# RJ45_4ch_Output.net
KiCad netlist of a schematic drawn in EAGLE
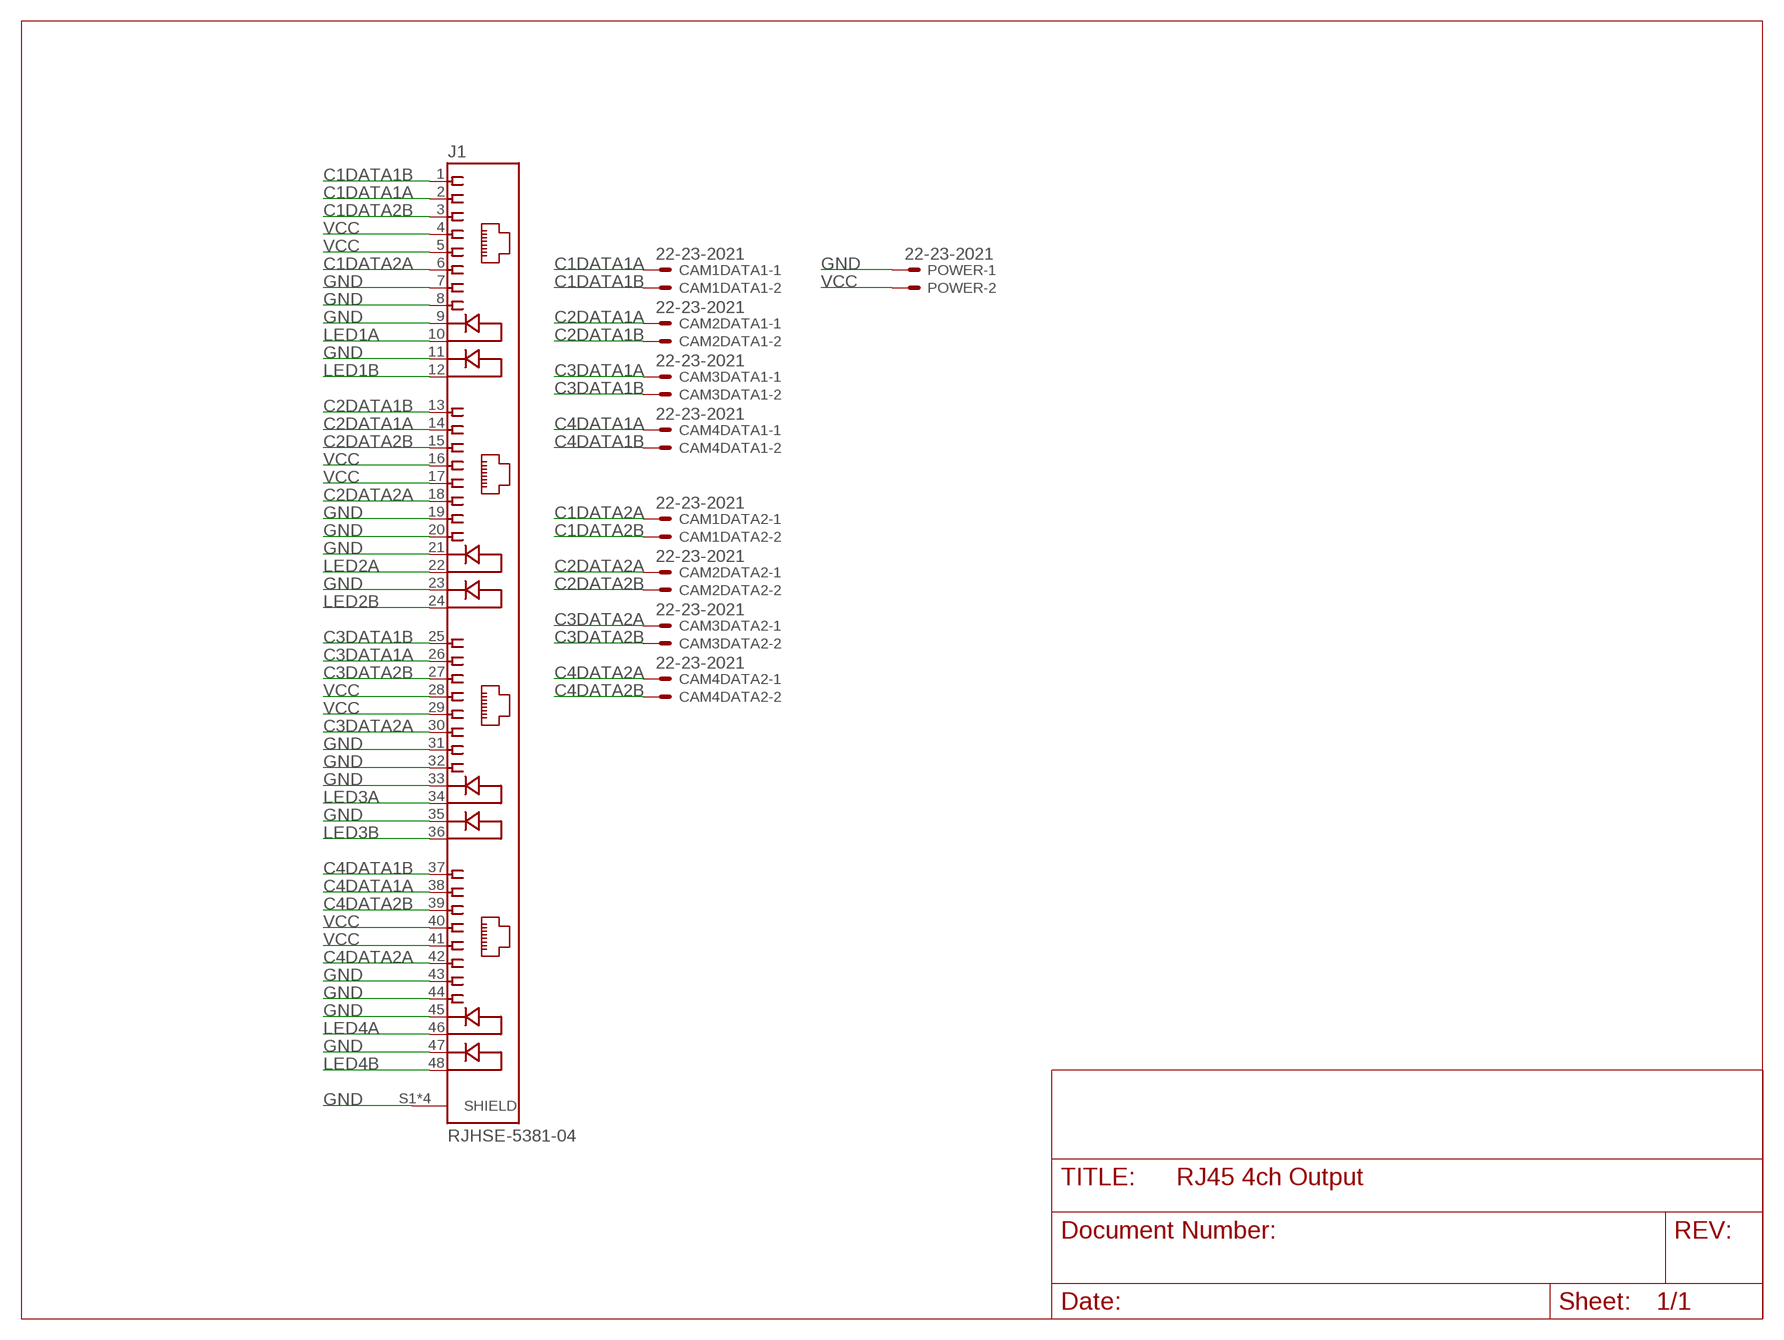
[diagram p0: schematic, sheet 1]

(export (version "E")
  (design (tool "Eeschema 10.0.6"))
  (components
    (comp (ref "CAM1DATA1")
      (value "22-23-2021")
      (footprint "eagle-import:22-23-2021")
      (fields (field (name "MF") "MOLEX"))
      (libsource (lib "eagle-import") (part "22-23-2021"))
    )
    (comp (ref "CAM1DATA2")
      (value "22-23-2021")
      (footprint "eagle-import:22-23-2021")
      (fields (field (name "MF") "MOLEX"))
      (libsource (lib "eagle-import") (part "22-23-2021"))
    )
    (comp (ref "CAM2DATA1")
      (value "22-23-2021")
      (footprint "eagle-import:22-23-2021")
      (fields (field (name "MF") "MOLEX"))
      (libsource (lib "eagle-import") (part "22-23-2021"))
    )
    (comp (ref "CAM2DATA2")
      (value "22-23-2021")
      (footprint "eagle-import:22-23-2021")
      (fields (field (name "MF") "MOLEX"))
      (libsource (lib "eagle-import") (part "22-23-2021"))
    )
    (comp (ref "CAM3DATA1")
      (value "22-23-2021")
      (footprint "eagle-import:22-23-2021")
      (fields (field (name "MF") "MOLEX"))
      (libsource (lib "eagle-import") (part "22-23-2021"))
    )
    (comp (ref "CAM3DATA2")
      (value "22-23-2021")
      (footprint "eagle-import:22-23-2021")
      (fields (field (name "MF") "MOLEX"))
      (libsource (lib "eagle-import") (part "22-23-2021"))
    )
    (comp (ref "CAM4DATA1")
      (value "22-23-2021")
      (footprint "eagle-import:22-23-2021")
      (fields (field (name "MF") "MOLEX"))
      (libsource (lib "eagle-import") (part "22-23-2021"))
    )
    (comp (ref "CAM4DATA2")
      (value "22-23-2021")
      (footprint "eagle-import:22-23-2021")
      (fields (field (name "MF") "MOLEX"))
      (libsource (lib "eagle-import") (part "22-23-2021"))
    )
    (comp (ref "J1")
      (value "RJHSE-5381-04")
      (footprint "eagle-import:AMPHENOL_RJHSE-5381-04")
      (fields (field (name "MF") "Amphenol ICC"))
      (libsource (lib "eagle-import") (part "RJHSE-5381-04"))
    )
    (comp (ref "POWER")
      (value "22-23-2021")
      (footprint "eagle-import:22-23-2021")
      (fields (field (name "MF") "MOLEX"))
      (libsource (lib "eagle-import") (part "22-23-2021"))
    )
  )
  (nets
    (net (code "1") (name "/C1DATA1A") (class "Default")
      (node (ref "CAM1DATA1") (pin "1") (pinfunction "S_1") (pintype "passive"))
      (node (ref "J1") (pin "2") (pinfunction "2_2") (pintype "passive"))
    )
    (net (code "2") (name "/C1DATA1B") (class "Default")
      (node (ref "CAM1DATA1") (pin "2") (pinfunction "S_2") (pintype "passive"))
      (node (ref "J1") (pin "1") (pinfunction "1_1") (pintype "passive"))
    )
    (net (code "3") (name "/C1DATA2A") (class "Default")
      (node (ref "CAM1DATA2") (pin "1") (pinfunction "S_1") (pintype "passive"))
      (node (ref "J1") (pin "6") (pinfunction "6_6") (pintype "passive"))
    )
    (net (code "4") (name "/C1DATA2B") (class "Default")
      (node (ref "CAM1DATA2") (pin "2") (pinfunction "S_2") (pintype "passive"))
      (node (ref "J1") (pin "3") (pinfunction "3_3") (pintype "passive"))
    )
    (net (code "5") (name "/C2DATA1A") (class "Default")
      (node (ref "CAM2DATA1") (pin "1") (pinfunction "S_1") (pintype "passive"))
      (node (ref "J1") (pin "14") (pinfunction "14_14") (pintype "passive"))
    )
    (net (code "6") (name "/C2DATA1B") (class "Default")
      (node (ref "CAM2DATA1") (pin "2") (pinfunction "S_2") (pintype "passive"))
      (node (ref "J1") (pin "13") (pinfunction "13_13") (pintype "passive"))
    )
    (net (code "7") (name "/C2DATA2A") (class "Default")
      (node (ref "CAM2DATA2") (pin "1") (pinfunction "S_1") (pintype "passive"))
      (node (ref "J1") (pin "18") (pinfunction "18_18") (pintype "passive"))
    )
    (net (code "8") (name "/C2DATA2B") (class "Default")
      (node (ref "CAM2DATA2") (pin "2") (pinfunction "S_2") (pintype "passive"))
      (node (ref "J1") (pin "15") (pinfunction "15_15") (pintype "passive"))
    )
    (net (code "9") (name "/C3DATA1A") (class "Default")
      (node (ref "CAM3DATA1") (pin "1") (pinfunction "S_1") (pintype "passive"))
      (node (ref "J1") (pin "26") (pinfunction "26_26") (pintype "passive"))
    )
    (net (code "10") (name "/C3DATA1B") (class "Default")
      (node (ref "CAM3DATA1") (pin "2") (pinfunction "S_2") (pintype "passive"))
      (node (ref "J1") (pin "25") (pinfunction "25_25") (pintype "passive"))
    )
    (net (code "11") (name "/C3DATA2A") (class "Default")
      (node (ref "CAM3DATA2") (pin "1") (pinfunction "S_1") (pintype "passive"))
      (node (ref "J1") (pin "30") (pinfunction "30_30") (pintype "passive"))
    )
    (net (code "12") (name "/C3DATA2B") (class "Default")
      (node (ref "CAM3DATA2") (pin "2") (pinfunction "S_2") (pintype "passive"))
      (node (ref "J1") (pin "27") (pinfunction "27_27") (pintype "passive"))
    )
    (net (code "13") (name "/C4DATA1A") (class "Default")
      (node (ref "CAM4DATA1") (pin "1") (pinfunction "S_1") (pintype "passive"))
      (node (ref "J1") (pin "38") (pinfunction "38_38") (pintype "passive"))
    )
    (net (code "14") (name "/C4DATA1B") (class "Default")
      (node (ref "CAM4DATA1") (pin "2") (pinfunction "S_2") (pintype "passive"))
      (node (ref "J1") (pin "37") (pinfunction "37_37") (pintype "passive"))
    )
    (net (code "15") (name "/C4DATA2A") (class "Default")
      (node (ref "CAM4DATA2") (pin "1") (pinfunction "S_1") (pintype "passive"))
      (node (ref "J1") (pin "42") (pinfunction "42_42") (pintype "passive"))
    )
    (net (code "16") (name "/C4DATA2B") (class "Default")
      (node (ref "CAM4DATA2") (pin "2") (pinfunction "S_2") (pintype "passive"))
      (node (ref "J1") (pin "39") (pinfunction "39_39") (pintype "passive"))
    )
    (net (code "17") (name "/GND") (class "Default")
      (node (ref "J1") (pin "11") (pinfunction "11_11") (pintype "passive"))
      (node (ref "J1") (pin "19") (pinfunction "19_19") (pintype "passive"))
      (node (ref "J1") (pin "20") (pinfunction "20_20") (pintype "passive"))
      (node (ref "J1") (pin "21") (pinfunction "21_21") (pintype "passive"))
      (node (ref "J1") (pin "23") (pinfunction "23_23") (pintype "passive"))
      (node (ref "J1") (pin "31") (pinfunction "31_31") (pintype "passive"))
      (node (ref "J1") (pin "32") (pinfunction "32_32") (pintype "passive"))
      (node (ref "J1") (pin "33") (pinfunction "33_33") (pintype "passive"))
      (node (ref "J1") (pin "35") (pinfunction "35_35") (pintype "passive"))
      (node (ref "J1") (pin "43") (pinfunction "43_43") (pintype "passive"))
      (node (ref "J1") (pin "44") (pinfunction "44_44") (pintype "passive"))
      (node (ref "J1") (pin "45") (pinfunction "45_45") (pintype "passive"))
      (node (ref "J1") (pin "47") (pinfunction "47_47") (pintype "passive"))
      (node (ref "J1") (pin "7") (pinfunction "7_7") (pintype "passive"))
      (node (ref "J1") (pin "8") (pinfunction "8_8") (pintype "passive"))
      (node (ref "J1") (pin "9") (pinfunction "9_9") (pintype "passive"))
      (node (ref "J1") (pin "S1") (pinfunction "SHIELD_S1") (pintype "passive"))
      (node (ref "J1") (pin "S2") (pinfunction "SHIELD_S2") (pintype "passive"))
      (node (ref "J1") (pin "S3") (pinfunction "SHIELD_S3") (pintype "passive"))
      (node (ref "J1") (pin "S4") (pinfunction "SHIELD_S4") (pintype "passive"))
      (node (ref "POWER") (pin "1") (pinfunction "S_1") (pintype "passive"))
    )
    (net (code "18") (name "/LED1A") (class "Default")
      (node (ref "J1") (pin "10") (pinfunction "10_10") (pintype "passive"))
    )
    (net (code "19") (name "/LED1B") (class "Default")
      (node (ref "J1") (pin "12") (pinfunction "12_12") (pintype "passive"))
    )
    (net (code "20") (name "/LED2A") (class "Default")
      (node (ref "J1") (pin "22") (pinfunction "22_22") (pintype "passive"))
    )
    (net (code "21") (name "/LED2B") (class "Default")
      (node (ref "J1") (pin "24") (pinfunction "24_24") (pintype "passive"))
    )
    (net (code "22") (name "/LED3A") (class "Default")
      (node (ref "J1") (pin "34") (pinfunction "34_34") (pintype "passive"))
    )
    (net (code "23") (name "/LED3B") (class "Default")
      (node (ref "J1") (pin "36") (pinfunction "36_36") (pintype "passive"))
    )
    (net (code "24") (name "/LED4A") (class "Default")
      (node (ref "J1") (pin "46") (pinfunction "46_46") (pintype "passive"))
    )
    (net (code "25") (name "/LED4B") (class "Default")
      (node (ref "J1") (pin "48") (pinfunction "48_48") (pintype "passive"))
    )
    (net (code "26") (name "/VCC") (class "Default")
      (node (ref "J1") (pin "16") (pinfunction "16_16") (pintype "passive"))
      (node (ref "J1") (pin "17") (pinfunction "17_17") (pintype "passive"))
      (node (ref "J1") (pin "28") (pinfunction "28_28") (pintype "passive"))
      (node (ref "J1") (pin "29") (pinfunction "29_29") (pintype "passive"))
      (node (ref "J1") (pin "4") (pinfunction "4_4") (pintype "passive"))
      (node (ref "J1") (pin "40") (pinfunction "40_40") (pintype "passive"))
      (node (ref "J1") (pin "41") (pinfunction "41_41") (pintype "passive"))
      (node (ref "J1") (pin "5") (pinfunction "5_5") (pintype "passive"))
      (node (ref "POWER") (pin "2") (pinfunction "S_2") (pintype "passive"))
    )
  )
)
